# LTC3092_BREAKOUT.net
KiCad netlist of a schematic drawn in EAGLE
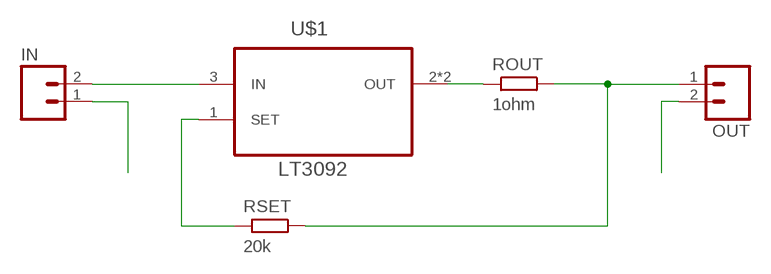
[diagram p0: schematic, sheet 1]

(export (version "E")
  (design (tool "Eeschema 10.0.6"))
  (components
    (comp (ref "IN")
      (value "M02PTH")
      (footprint "eagle-import:1X02")
      (libsource (lib "eagle-import") (part "M02PTH"))
    )
    (comp (ref "OUT")
      (value "M02PTH")
      (footprint "eagle-import:1X02")
      (libsource (lib "eagle-import") (part "M02PTH"))
    )
    (comp (ref "ROUT")
      (value "1ohm")
      (footprint "eagle-import:R0603-N")
      (libsource (lib "eagle-import") (part "RESISTOR0603-N"))
    )
    (comp (ref "RSET")
      (value "20k")
      (footprint "eagle-import:R0603-N")
      (libsource (lib "eagle-import") (part "RESISTOR0603-N"))
    )
    (comp (ref "U$1")
      (value "LT3092")
      (footprint "eagle-import:SOT223")
      (libsource (lib "eagle-import") (part "LT3092"))
    )
  )
  (nets
    (net (code "1") (name "/GND") (class "Default")
      (node (ref "IN") (pin "1") (pinfunction "1_1") (pintype "passive"))
      (node (ref "OUT") (pin "2") (pinfunction "2_2") (pintype "passive"))
    )
    (net (code "2") (name "Net-(ROUT-P$1)") (class "Default")
      (node (ref "ROUT") (pin "1") (pinfunction "P$1_1") (pintype "passive"))
      (node (ref "U$1") (pin "2") (pinfunction "OUT_2") (pintype "output"))
      (node (ref "U$1") (pin "4") (pinfunction "OUT_4") (pintype "output"))
    )
    (net (code "3") (name "Net-(ROUT-P$2)") (class "Default")
      (node (ref "OUT") (pin "1") (pinfunction "1_1") (pintype "passive"))
      (node (ref "ROUT") (pin "2") (pinfunction "P$2_2") (pintype "passive"))
      (node (ref "RSET") (pin "2") (pinfunction "P$2_2") (pintype "passive"))
    )
    (net (code "4") (name "Net-(RSET-P$1)") (class "Default")
      (node (ref "RSET") (pin "1") (pinfunction "P$1_1") (pintype "passive"))
      (node (ref "U$1") (pin "1") (pinfunction "SET_1") (pintype "input"))
    )
    (net (code "5") (name "Net-(U$1-IN)") (class "Default")
      (node (ref "IN") (pin "2") (pinfunction "2_2") (pintype "passive"))
      (node (ref "U$1") (pin "3") (pinfunction "IN_3") (pintype "power_in"))
    )
  )
)
